# MotorBoardHoles.net
KiCad netlist of a schematic drawn in EAGLE
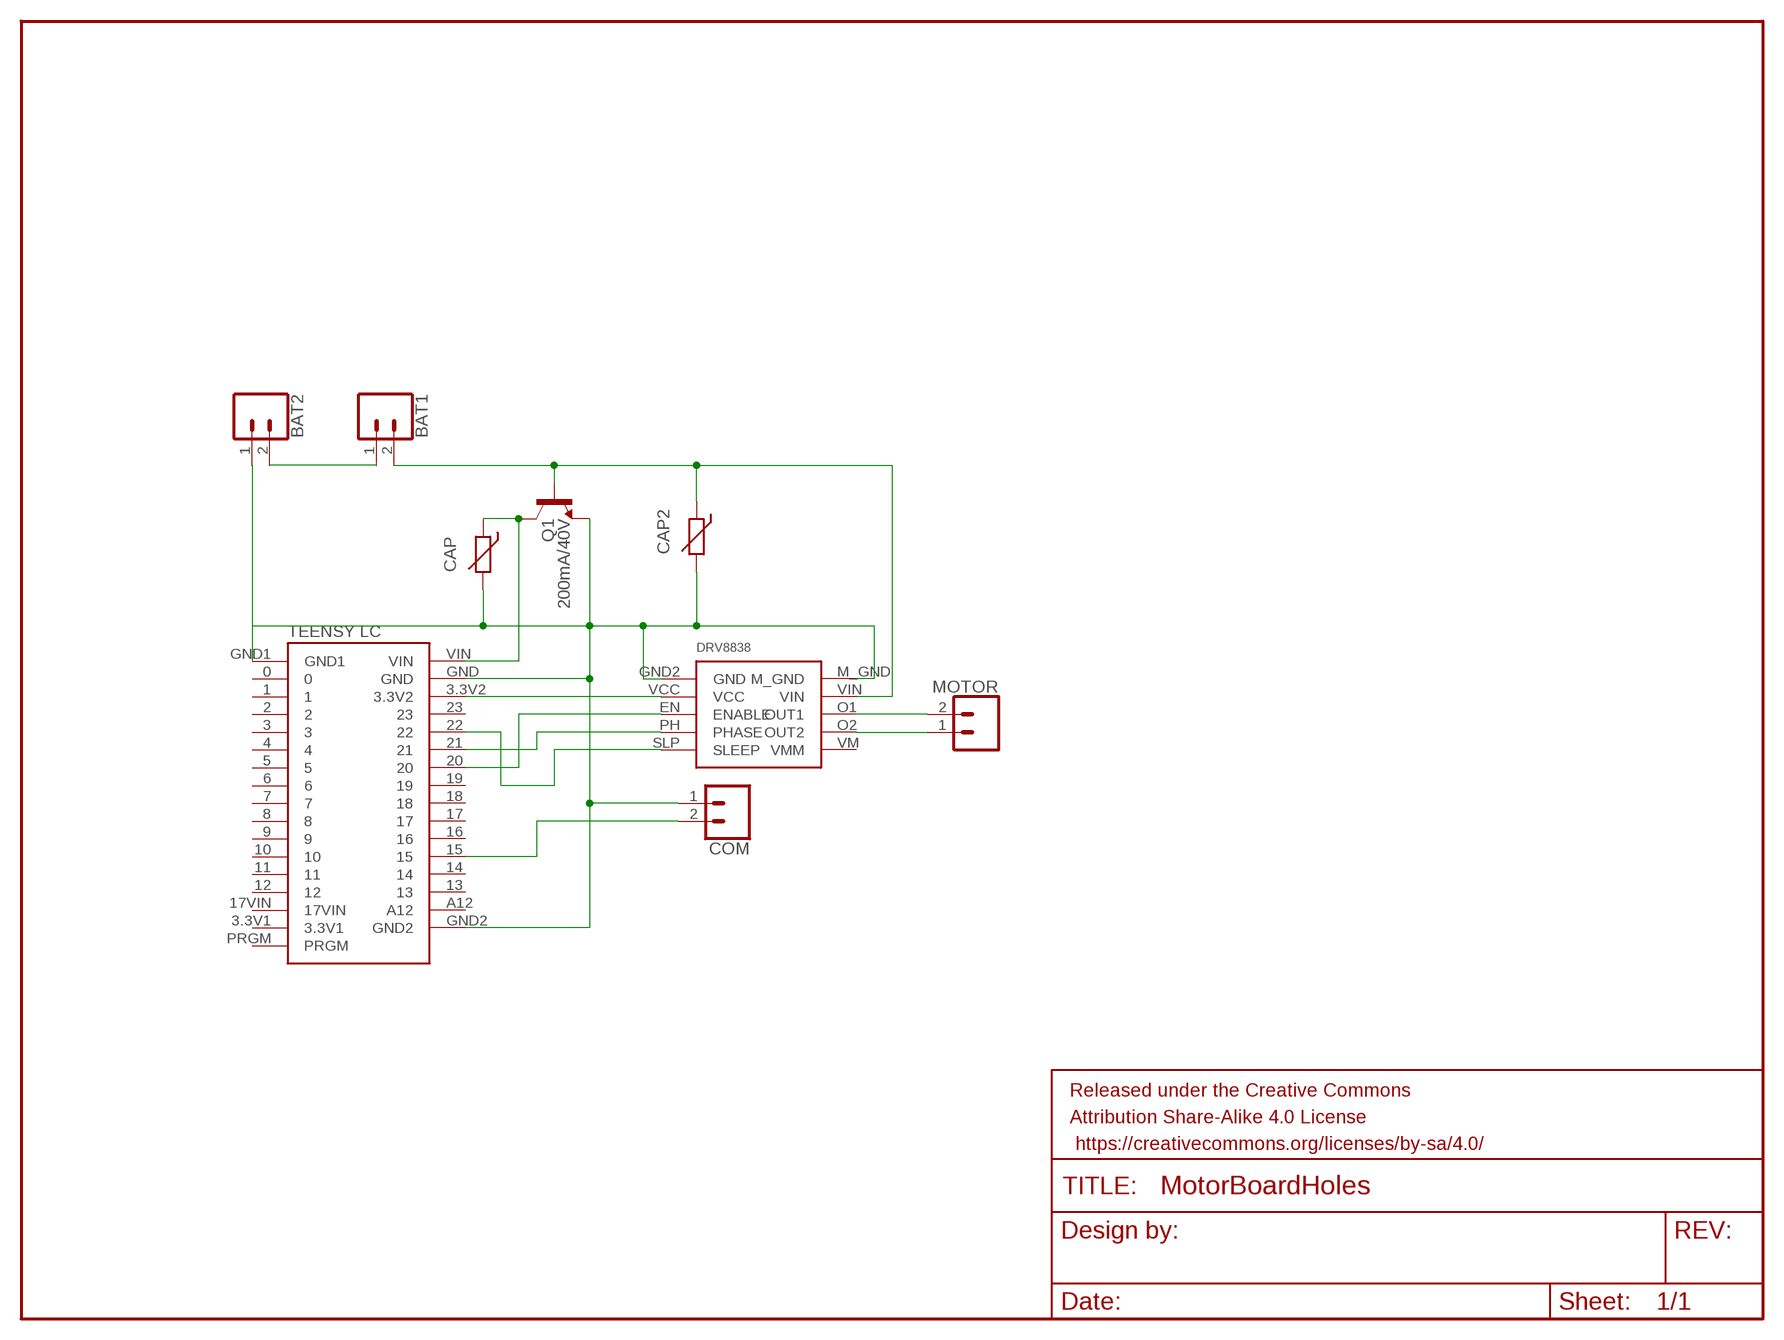
[diagram p0: schematic, sheet 1]

(export (version "E")
  (design (tool "Eeschema 10.0.6"))
  (components
    (comp (ref "BAT1")
      (value "CONN_02JST-PTH-2")
      (footprint "eagle-import:JST-2-PTH")
      (libsource (lib "eagle-import") (part "CONN_02JST-PTH-2"))
    )
    (comp (ref "BAT2")
      (value "CONN_02JST-PTH-2")
      (footprint "eagle-import:JST-2-PTH")
      (libsource (lib "eagle-import") (part "CONN_02JST-PTH-2"))
    )
    (comp (ref "CAP")
      (value "THERMISTOR_R-5")
      (footprint "eagle-import:R-5")
      (libsource (lib "eagle-import") (part "THERMISTOR_R-5"))
    )
    (comp (ref "CAP2")
      (value "THERMISTOR_R-5")
      (footprint "eagle-import:R-5")
      (libsource (lib "eagle-import") (part "THERMISTOR_R-5"))
    )
    (comp (ref "COM")
      (value "CONN_02JST-PTH-2")
      (footprint "eagle-import:JST-2-PTH")
      (libsource (lib "eagle-import") (part "CONN_02JST-PTH-2"))
    )
    (comp (ref "FRAME1")
      (value "FRAME-LETTER")
      (footprint "eagle-import:CREATIVE_COMMONS")
      (libsource (lib "eagle-import") (part "FRAME-LETTER"))
    )
    (comp (ref "MOTOR")
      (value "CONN_02JST-PTH-2")
      (footprint "eagle-import:JST-2-PTH")
      (libsource (lib "eagle-import") (part "CONN_02JST-PTH-2"))
    )
    (comp (ref "Q1")
      (value "200mA/40V")
      (footprint "eagle-import:TO-92")
      (libsource (lib "eagle-import") (part "TRANS_NPN-2N3904"))
    )
    (comp (ref "U$1")
      (value "TEENSYLC")
      (footprint "eagle-import:TEENSYLC")
      (libsource (lib "eagle-import") (part "TEENSYLC"))
    )
    (comp (ref "U$2")
      (value "POLOLU_DRV8838")
      (footprint "eagle-import:POLOLU_DRV8838")
      (libsource (lib "eagle-import") (part "POLOLU_DRV8838"))
    )
  )
  (nets
    (net (code "1") (name "Net-(BAT1-Pad1)") (class "Default")
      (node (ref "BAT1") (pin "1") (pinfunction "1_1") (pintype "passive"))
      (node (ref "BAT2") (pin "2") (pinfunction "2_2") (pintype "passive"))
    )
    (net (code "2") (name "Net-(COM-Pad2)") (class "Default")
      (node (ref "COM") (pin "2") (pinfunction "2_2") (pintype "passive"))
      (node (ref "U$1") (pin "15") (pinfunction "15_15") (pintype "bidirectional"))
    )
    (net (code "3") (name "Net-(Q1-B)") (class "Default")
      (node (ref "BAT1") (pin "2") (pinfunction "2_2") (pintype "passive"))
      (node (ref "CAP2") (pin "1") (pinfunction "1_1") (pintype "passive"))
      (node (ref "Q1") (pin "2") (pinfunction "B_2") (pintype "passive"))
      (node (ref "U$2") (pin "VIN") (pinfunction "VIN_VIN") (pintype "bidirectional"))
    )
    (net (code "4") (name "Net-(Q1-C)") (class "Default")
      (node (ref "CAP") (pin "1") (pinfunction "1_1") (pintype "passive"))
      (node (ref "Q1") (pin "3") (pinfunction "C_3") (pintype "passive"))
      (node (ref "U$1") (pin "VIN") (pinfunction "VIN_VIN") (pintype "bidirectional"))
    )
    (net (code "5") (name "Net-(Q1-E)") (class "Default")
      (node (ref "BAT2") (pin "1") (pinfunction "1_1") (pintype "passive"))
      (node (ref "CAP") (pin "2") (pinfunction "2_2") (pintype "passive"))
      (node (ref "CAP2") (pin "2") (pinfunction "2_2") (pintype "passive"))
      (node (ref "COM") (pin "1") (pinfunction "1_1") (pintype "passive"))
      (node (ref "Q1") (pin "1") (pinfunction "E_1") (pintype "passive"))
      (node (ref "U$1") (pin "GND") (pinfunction "GND_GND") (pintype "bidirectional"))
      (node (ref "U$1") (pin "GND1") (pinfunction "GND1_GND1") (pintype "bidirectional"))
      (node (ref "U$1") (pin "GND2") (pinfunction "GND2_GND2") (pintype "bidirectional"))
      (node (ref "U$2") (pin "GND2") (pinfunction "GND_GND2") (pintype "bidirectional"))
      (node (ref "U$2") (pin "M_GND") (pinfunction "M_GND_M_GND") (pintype "bidirectional"))
    )
    (net (code "6") (name "Net-(U$1-Pad3.3V2)") (class "Default")
      (node (ref "U$1") (pin "3.3V2") (pinfunction "3.3V2_3.3V2") (pintype "bidirectional"))
      (node (ref "U$2") (pin "VCC") (pinfunction "VCC_VCC") (pintype "bidirectional"))
    )
    (net (code "7") (name "Net-(U$2-ENABLE)") (class "Default")
      (node (ref "U$1") (pin "20") (pinfunction "20_20") (pintype "bidirectional"))
      (node (ref "U$2") (pin "EN") (pinfunction "ENABLE_EN") (pintype "bidirectional"))
    )
    (net (code "8") (name "Net-(U$2-OUT1)") (class "Default")
      (node (ref "MOTOR") (pin "2") (pinfunction "2_2") (pintype "passive"))
      (node (ref "U$2") (pin "O1") (pinfunction "OUT1_O1") (pintype "bidirectional"))
    )
    (net (code "9") (name "Net-(U$2-OUT2)") (class "Default")
      (node (ref "MOTOR") (pin "1") (pinfunction "1_1") (pintype "passive"))
      (node (ref "U$2") (pin "O2") (pinfunction "OUT2_O2") (pintype "bidirectional"))
    )
    (net (code "10") (name "Net-(U$2-PHASE)") (class "Default")
      (node (ref "U$1") (pin "21") (pinfunction "21_21") (pintype "bidirectional"))
      (node (ref "U$2") (pin "PH") (pinfunction "PHASE_PH") (pintype "bidirectional"))
    )
    (net (code "11") (name "Net-(U$2-SLEEP)") (class "Default")
      (node (ref "U$1") (pin "22") (pinfunction "22_22") (pintype "bidirectional"))
      (node (ref "U$2") (pin "SLP") (pinfunction "SLEEP_SLP") (pintype "bidirectional"))
    )
    (net (code "12") (name "unconnected-(U$1-Pad0)") (class "Default")
      (node (ref "U$1") (pin "0") (pinfunction "0_0") (pintype "bidirectional"))
    )
    (net (code "13") (name "unconnected-(U$1-Pad1)") (class "Default")
      (node (ref "U$1") (pin "1") (pinfunction "1_1") (pintype "bidirectional"))
    )
    (net (code "14") (name "unconnected-(U$1-Pad2)") (class "Default")
      (node (ref "U$1") (pin "2") (pinfunction "2_2") (pintype "bidirectional"))
    )
    (net (code "15") (name "unconnected-(U$1-Pad3)") (class "Default")
      (node (ref "U$1") (pin "3") (pinfunction "3_3") (pintype "bidirectional"))
    )
    (net (code "16") (name "unconnected-(U$1-Pad3.3V1)") (class "Default")
      (node (ref "U$1") (pin "3.3V1") (pinfunction "3.3V1_3.3V1") (pintype "bidirectional"))
    )
    (net (code "17") (name "unconnected-(U$1-Pad4)") (class "Default")
      (node (ref "U$1") (pin "4") (pinfunction "4_4") (pintype "bidirectional"))
    )
    (net (code "18") (name "unconnected-(U$1-Pad5)") (class "Default")
      (node (ref "U$1") (pin "5") (pinfunction "5_5") (pintype "bidirectional"))
    )
    (net (code "19") (name "unconnected-(U$1-Pad6)") (class "Default")
      (node (ref "U$1") (pin "6") (pinfunction "6_6") (pintype "bidirectional"))
    )
    (net (code "20") (name "unconnected-(U$1-Pad7)") (class "Default")
      (node (ref "U$1") (pin "7") (pinfunction "7_7") (pintype "bidirectional"))
    )
    (net (code "21") (name "unconnected-(U$1-Pad8)") (class "Default")
      (node (ref "U$1") (pin "8") (pinfunction "8_8") (pintype "bidirectional"))
    )
    (net (code "22") (name "unconnected-(U$1-Pad9)") (class "Default")
      (node (ref "U$1") (pin "9") (pinfunction "9_9") (pintype "bidirectional"))
    )
    (net (code "23") (name "unconnected-(U$1-Pad10)") (class "Default")
      (node (ref "U$1") (pin "10") (pinfunction "10_10") (pintype "bidirectional"))
    )
    (net (code "24") (name "unconnected-(U$1-Pad11)") (class "Default")
      (node (ref "U$1") (pin "11") (pinfunction "11_11") (pintype "bidirectional"))
    )
    (net (code "25") (name "unconnected-(U$1-Pad12)") (class "Default")
      (node (ref "U$1") (pin "12") (pinfunction "12_12") (pintype "bidirectional"))
    )
    (net (code "26") (name "unconnected-(U$1-Pad13)") (class "Default")
      (node (ref "U$1") (pin "13") (pinfunction "13_13") (pintype "bidirectional"))
    )
    (net (code "27") (name "unconnected-(U$1-Pad14)") (class "Default")
      (node (ref "U$1") (pin "14") (pinfunction "14_14") (pintype "bidirectional"))
    )
    (net (code "28") (name "unconnected-(U$1-Pad16)") (class "Default")
      (node (ref "U$1") (pin "16") (pinfunction "16_16") (pintype "bidirectional"))
    )
    (net (code "29") (name "unconnected-(U$1-Pad17)") (class "Default")
      (node (ref "U$1") (pin "17") (pinfunction "17_17") (pintype "bidirectional"))
    )
    (net (code "30") (name "unconnected-(U$1-Pad17VIN)") (class "Default")
      (node (ref "U$1") (pin "17VIN") (pinfunction "17VIN_17VIN") (pintype "bidirectional"))
    )
    (net (code "31") (name "unconnected-(U$1-Pad18)") (class "Default")
      (node (ref "U$1") (pin "18") (pinfunction "18_18") (pintype "bidirectional"))
    )
    (net (code "32") (name "unconnected-(U$1-Pad19)") (class "Default")
      (node (ref "U$1") (pin "19") (pinfunction "19_19") (pintype "bidirectional"))
    )
    (net (code "33") (name "unconnected-(U$1-Pad23)") (class "Default")
      (node (ref "U$1") (pin "23") (pinfunction "23_23") (pintype "bidirectional"))
    )
    (net (code "34") (name "unconnected-(U$1-PadA12)") (class "Default")
      (node (ref "U$1") (pin "A12") (pinfunction "A12_A12") (pintype "bidirectional"))
    )
    (net (code "35") (name "unconnected-(U$1-PadPRGM)") (class "Default")
      (node (ref "U$1") (pin "PRGM") (pinfunction "PRGM_PRGM") (pintype "bidirectional"))
    )
    (net (code "36") (name "unconnected-(U$2-VMM-PadVM)") (class "Default")
      (node (ref "U$2") (pin "VM") (pinfunction "VMM_VM") (pintype "bidirectional"))
    )
  )
)
